# untitled1.net
KiCad netlist of a schematic drawn in EAGLE
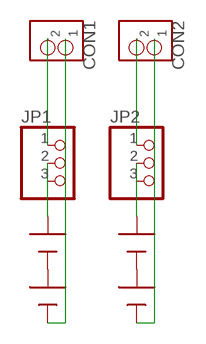
[diagram p0: schematic, sheet 1]

(export (version "E")
  (design (tool "Eeschema 10.0.6"))
  (components
    (comp (ref "CON1")
      (value "B2B-XH-A")
      (footprint "eagle-import:B2B-XH-A")
      (libsource (lib "eagle-import") (part "B2B-XH-A"))
    )
    (comp (ref "CON2")
      (value "B2B-XH-A")
      (footprint "eagle-import:B2B-XH-A")
      (libsource (lib "eagle-import") (part "B2B-XH-A"))
    )
    (comp (ref "JP1")
      (value "PINHD-1X3")
      (footprint "eagle-import:1X03")
      (libsource (lib "eagle-import") (part "PINHD-1X3"))
    )
    (comp (ref "JP2")
      (value "PINHD-1X3")
      (footprint "eagle-import:1X03")
      (libsource (lib "eagle-import") (part "PINHD-1X3"))
    )
    (comp (ref "U$1")
      (value "CR123A")
      (footprint "eagle-import:CR123A")
      (libsource (lib "eagle-import") (part "CR123A"))
    )
    (comp (ref "U$2")
      (value "CR123A")
      (footprint "eagle-import:CR123A")
      (libsource (lib "eagle-import") (part "CR123A"))
    )
    (comp (ref "U$3")
      (value "CR123A")
      (footprint "eagle-import:CR123A")
      (libsource (lib "eagle-import") (part "CR123A"))
    )
    (comp (ref "U$4")
      (value "CR123A")
      (footprint "eagle-import:CR123A")
      (libsource (lib "eagle-import") (part "CR123A"))
    )
  )
  (nets
    (net (code "1") (name "Net-(CON1-1)") (class "Default")
      (node (ref "CON1") (pin "P$1") (pinfunction "1_P$1") (pintype "bidirectional"))
      (node (ref "U$3") (pin "-") (pinfunction "-_-") (pintype "power_in"))
    )
    (net (code "2") (name "Net-(CON1-2)") (class "Default")
      (node (ref "CON1") (pin "P$2") (pinfunction "2_P$2") (pintype "bidirectional"))
      (node (ref "JP1") (pin "1") (pinfunction "1_1") (pintype "passive"))
    )
    (net (code "3") (name "Net-(CON2-1)") (class "Default")
      (node (ref "CON2") (pin "P$1") (pinfunction "1_P$1") (pintype "bidirectional"))
      (node (ref "U$4") (pin "-") (pinfunction "-_-") (pintype "power_in"))
    )
    (net (code "4") (name "Net-(CON2-2)") (class "Default")
      (node (ref "CON2") (pin "P$2") (pinfunction "2_P$2") (pintype "bidirectional"))
      (node (ref "JP2") (pin "1") (pinfunction "1_1") (pintype "passive"))
    )
    (net (code "5") (name "Net-(JP1-Pad2)") (class "Default")
      (node (ref "JP1") (pin "2") (pinfunction "2_2") (pintype "passive"))
      (node (ref "JP1") (pin "3") (pinfunction "3_3") (pintype "passive"))
      (node (ref "U$1") (pin "+") (pinfunction "+_+") (pintype "power_in"))
    )
    (net (code "6") (name "Net-(JP2-Pad2)") (class "Default")
      (node (ref "JP2") (pin "2") (pinfunction "2_2") (pintype "passive"))
      (node (ref "JP2") (pin "3") (pinfunction "3_3") (pintype "passive"))
      (node (ref "U$2") (pin "+") (pinfunction "+_+") (pintype "power_in"))
    )
    (net (code "7") (name "Net-(U$1-Pad-)") (class "Default")
      (node (ref "U$1") (pin "-") (pinfunction "-_-") (pintype "power_in"))
      (node (ref "U$3") (pin "+") (pinfunction "+_+") (pintype "power_in"))
    )
    (net (code "8") (name "Net-(U$2-Pad-)") (class "Default")
      (node (ref "U$2") (pin "-") (pinfunction "-_-") (pintype "power_in"))
      (node (ref "U$4") (pin "+") (pinfunction "+_+") (pintype "power_in"))
    )
  )
)
